# DevBoard_20240716.net
KiCad netlist of a schematic drawn in EasyEDA Pro
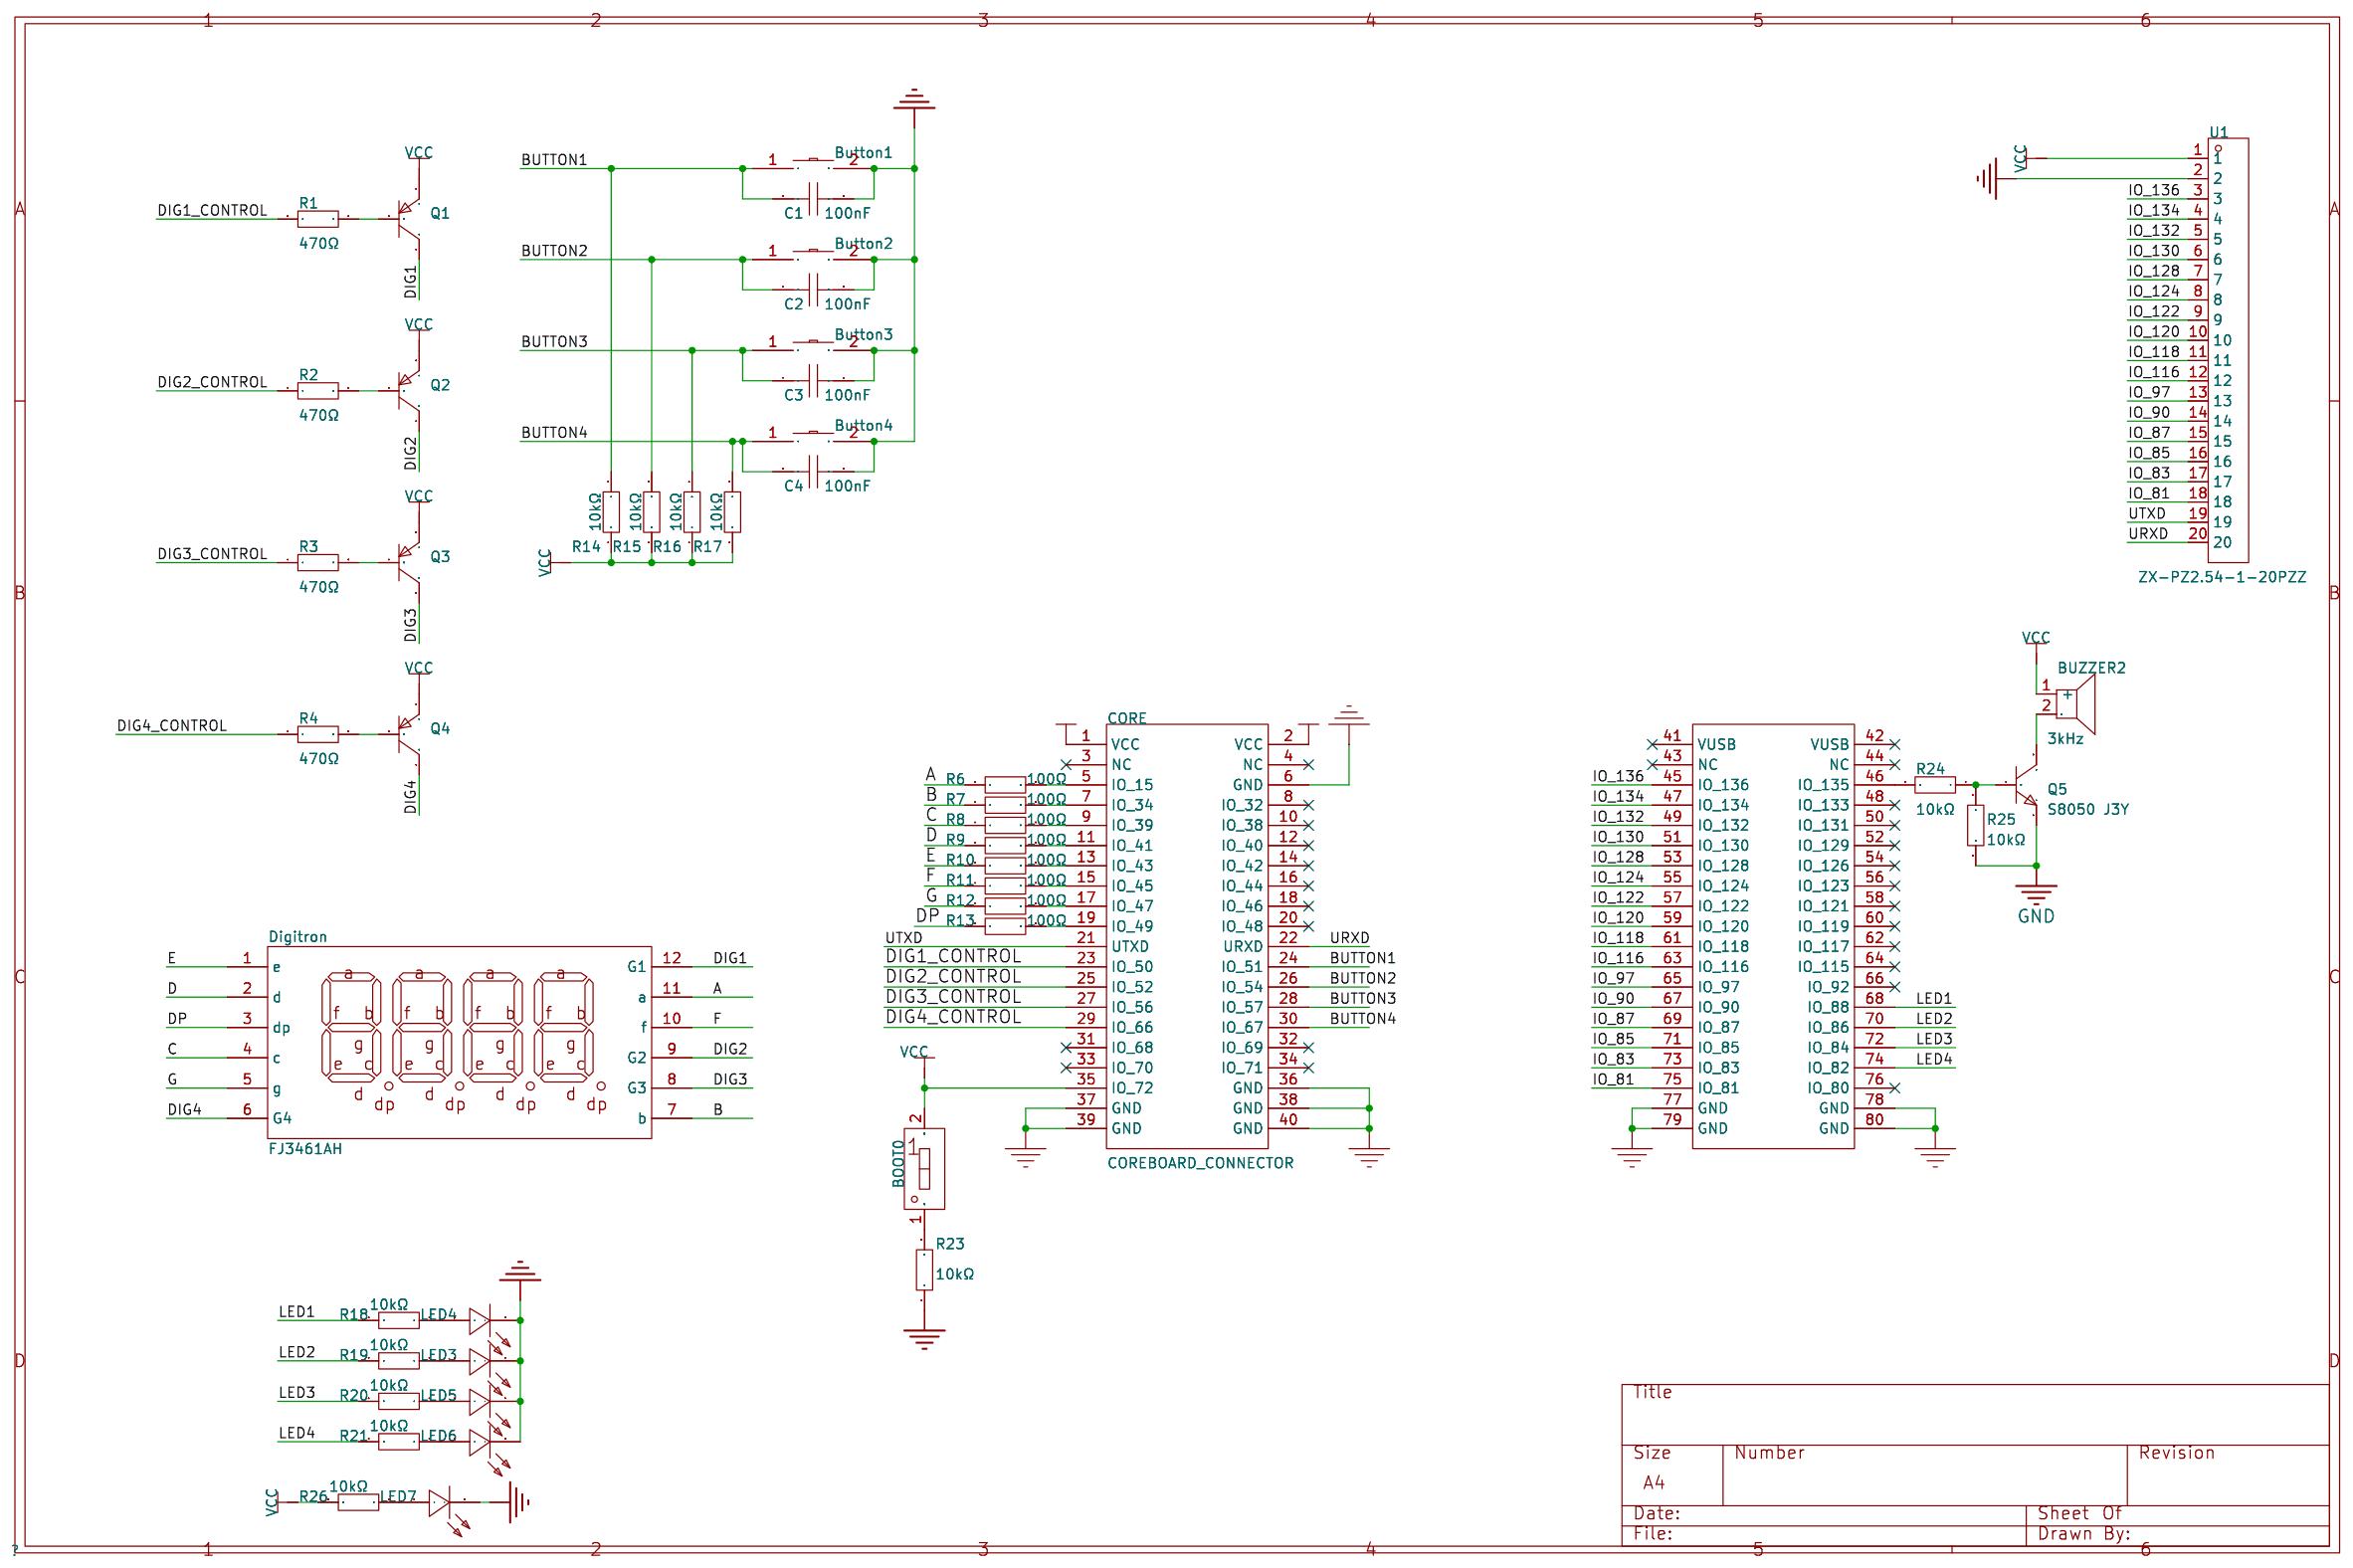
[diagram p0: schematic sheet]

(export (version "E")
  (design (tool "Eeschema 10.0.6"))
  (components
    (comp (ref "BOOT0")
      (value "DSIC01LS-P")
      (footprint "easyedapro:SW-SMD_2P-L3.5-W6.2-P2.54-LS9.8")
      (description "类型:平拨,凸起式;电路结构:单刀单掷;开关位数:1位;额定电流:25mA;额定电压:24V;使用寿命:3千次;颜色:黑色;")
      (fields (field (name "Manufacturer") "XKB Connectivity(中国星坤)"))
      (libsource (lib "easyedapro") (part "DSIC01LS-P_C600988"))
    )
    (comp (ref "Button1")
      (value "TS-1101-C-W")
      (footprint "easyedapro:SW-SMD_L6.0-W3.3-LS8.0")
      (fields (field (name "Manufacturer") "XKB Connectivity(中国星坤)"))
      (libsource (lib "easyedapro") (part "TS-1101-C-W"))
    )
    (comp (ref "Button2")
      (value "TS-1101-C-W")
      (footprint "easyedapro:SW-SMD_L6.0-W3.3-LS8.0")
      (fields (field (name "Manufacturer") "XKB Connectivity(中国星坤)"))
      (libsource (lib "easyedapro") (part "TS-1101-C-W"))
    )
    (comp (ref "Button3")
      (value "TS-1101-C-W")
      (footprint "easyedapro:SW-SMD_L6.0-W3.3-LS8.0")
      (fields (field (name "Manufacturer") "XKB Connectivity(中国星坤)"))
      (libsource (lib "easyedapro") (part "TS-1101-C-W"))
    )
    (comp (ref "Button4")
      (value "TS-1101-C-W")
      (footprint "easyedapro:SW-SMD_L6.0-W3.3-LS8.0")
      (fields (field (name "Manufacturer") "XKB Connectivity(中国星坤)"))
      (libsource (lib "easyedapro") (part "TS-1101-C-W"))
    )
    (comp (ref "BUZZER2")
      (value "3kHz")
      (footprint "easyedapro:BUZ-TH_BD9.6-P5.00-D0.7-FD")
      (description "驱动方式:有源(内含驱动线路);构造类型:电磁式;频率:3kHz;声压(SPL):85dB;")
      (fields (field (name "Manufacturer Part") "HNB09A05") (field (name "Manufacturer") "华能"))
      (libsource (lib "easyedapro") (part "HNB09A05"))
    )
    (comp (ref "C1")
      (value "100nF")
      (footprint "easyedapro:C0603")
      (description "容值:100nF;精度:±10%;额定电压:50V;材质(温度系数):X7R;")
      (fields
        (field (name "Manufacturer Part") "CC0603KRX7R9BB104")
        (field (name "Manufacturer") "YAGEO(国巨)")
      )
      (libsource (lib "easyedapro") (part "CC0603KRX7R9BB104"))
    )
    (comp (ref "C2")
      (value "100nF")
      (footprint "easyedapro:C0603")
      (description "容值:100nF;精度:±10%;额定电压:50V;材质(温度系数):X7R;")
      (fields
        (field (name "Manufacturer Part") "CC0603KRX7R9BB104")
        (field (name "Manufacturer") "YAGEO(国巨)")
      )
      (libsource (lib "easyedapro") (part "CC0603KRX7R9BB104"))
    )
    (comp (ref "C3")
      (value "100nF")
      (footprint "easyedapro:C0603")
      (description "容值:100nF;精度:±10%;额定电压:50V;材质(温度系数):X7R;")
      (fields
        (field (name "Manufacturer Part") "CC0603KRX7R9BB104")
        (field (name "Manufacturer") "YAGEO(国巨)")
      )
      (libsource (lib "easyedapro") (part "CC0603KRX7R9BB104"))
    )
    (comp (ref "C4")
      (value "100nF")
      (footprint "easyedapro:C0603")
      (description "容值:100nF;精度:±10%;额定电压:50V;材质(温度系数):X7R;")
      (fields
        (field (name "Manufacturer Part") "CC0603KRX7R9BB104")
        (field (name "Manufacturer") "YAGEO(国巨)")
      )
      (libsource (lib "easyedapro") (part "CC0603KRX7R9BB104"))
    )
    (comp (ref "CORE")
      (value "COREBOARD_CONNECTOR")
      (libsource (lib "easyedapro") (part "COREBOARD_CONNECTOR"))
    )
    (comp (ref "Digitron")
      (value "FJ3461AH")
      (footprint "easyedapro:LED-SEG-TH_12P-L30.0-W14.0-P2.54-S10.16-BL")
      (description "数码管位数:4位;功耗:-;发光颜色:红色;LED极性:共阴极;数字/字母大小(英寸):0.36;")
      (fields (field (name "Manufacturer") "志浩"))
      (libsource (lib "easyedapro") (part "FJ3461AH"))
    )
    (comp (ref "LED3")
      (value "NCD0805B2")
      (footprint "easyedapro:LED0805-R-RD")
      (fields (field (name "Manufacturer") "国星光电"))
      (libsource (lib "easyedapro") (part "FC-A2012BK-470H2"))
    )
    (comp (ref "LED4")
      (value "NCD0805B2")
      (footprint "easyedapro:LED0805-R-RD")
      (fields (field (name "Manufacturer") "国星光电"))
      (libsource (lib "easyedapro") (part "FC-A2012BK-470H2"))
    )
    (comp (ref "LED5")
      (value "NCD0805B2")
      (footprint "easyedapro:LED0805-R-RD")
      (fields (field (name "Manufacturer") "国星光电"))
      (libsource (lib "easyedapro") (part "FC-A2012BK-470H2"))
    )
    (comp (ref "LED6")
      (value "NCD0805B2")
      (footprint "easyedapro:LED0805-R-RD")
      (fields (field (name "Manufacturer") "国星光电"))
      (libsource (lib "easyedapro") (part "FC-A2012BK-470H2"))
    )
    (comp (ref "LED7")
      (value "NCD0805B2")
      (footprint "easyedapro:LED0805-R-RD")
      (fields (field (name "Manufacturer") "国星光电"))
      (libsource (lib "easyedapro") (part "FC-A2012BK-470H2"))
    )
    (comp (ref "Q1")
      (value "~")
      (footprint "easyedapro:S8550P_SOT")
      (libsource (lib "easyedapro") (part "PNP"))
    )
    (comp (ref "Q2")
      (value "~")
      (footprint "easyedapro:S8550P_SOT")
      (libsource (lib "easyedapro") (part "PNP"))
    )
    (comp (ref "Q3")
      (value "~")
      (footprint "easyedapro:S8550P_SOT")
      (libsource (lib "easyedapro") (part "PNP"))
    )
    (comp (ref "Q4")
      (value "~")
      (footprint "easyedapro:S8550P_SOT")
      (libsource (lib "easyedapro") (part "PNP"))
    )
    (comp (ref "Q5")
      (value "S8050 J3Y")
      (footprint "easyedapro:SOT-23-3_L3.0-W1.7-P0.95-LS2.9-BR")
      (description "晶体管类型:NPN;集射极击穿电压(Vceo):25V;集电极电流(Ic):500mA;功率(Pd):300mW;直流电流增益(hFE@Ic,Vce):200@50mA,1V;")
      (fields (field (name "Manufacturer") "CJ(江苏长电/长晶)"))
      (libsource (lib "easyedapro") (part "S8050_C2146"))
    )
    (comp (ref "R1")
      (value "470Ω")
      (footprint "easyedapro:R0603")
      (description "电阻类型:厚膜电阻;阻值:470Ω;精度:±1%;功率:100mW;最大工作电压:75V;温度系数:±100ppm/°C;")
      (fields
        (field (name "Manufacturer Part") "0603WAF4700T5E")
        (field (name "Manufacturer") "UNI-ROYAL(厚声)")
      )
      (libsource (lib "easyedapro") (part "0603WAF4700T5E"))
    )
    (comp (ref "R2")
      (value "470Ω")
      (footprint "easyedapro:R0603")
      (description "电阻类型:厚膜电阻;阻值:470Ω;精度:±1%;功率:100mW;最大工作电压:75V;温度系数:±100ppm/°C;")
      (fields
        (field (name "Manufacturer Part") "0603WAF4700T5E")
        (field (name "Manufacturer") "UNI-ROYAL(厚声)")
      )
      (libsource (lib "easyedapro") (part "0603WAF4700T5E"))
    )
    (comp (ref "R3")
      (value "470Ω")
      (footprint "easyedapro:R0603")
      (description "电阻类型:厚膜电阻;阻值:470Ω;精度:±1%;功率:100mW;最大工作电压:75V;温度系数:±100ppm/°C;")
      (fields
        (field (name "Manufacturer Part") "0603WAF4700T5E")
        (field (name "Manufacturer") "UNI-ROYAL(厚声)")
      )
      (libsource (lib "easyedapro") (part "0603WAF4700T5E"))
    )
    (comp (ref "R4")
      (value "470Ω")
      (footprint "easyedapro:R0603")
      (description "电阻类型:厚膜电阻;阻值:470Ω;精度:±1%;功率:100mW;最大工作电压:75V;温度系数:±100ppm/°C;")
      (fields
        (field (name "Manufacturer Part") "0603WAF4700T5E")
        (field (name "Manufacturer") "UNI-ROYAL(厚声)")
      )
      (libsource (lib "easyedapro") (part "0603WAF4700T5E"))
    )
    (comp (ref "R6")
      (value "100Ω")
      (footprint "easyedapro:R0603")
      (description "电阻类型:厚膜电阻;阻值:100Ω;精度:±1%;功率:100mW;最大工作电压:75V;温度系数:±200ppm/°C;")
      (fields
        (field (name "Manufacturer Part") "0603WAF1000T5E")
        (field (name "Manufacturer") "UNI-ROYAL(厚声)")
      )
      (libsource (lib "easyedapro") (part "0603WAF1000T5E"))
    )
    (comp (ref "R7")
      (value "100Ω")
      (footprint "easyedapro:R0603")
      (description "电阻类型:厚膜电阻;阻值:100Ω;精度:±1%;功率:100mW;最大工作电压:75V;温度系数:±200ppm/°C;")
      (fields
        (field (name "Manufacturer Part") "0603WAF1000T5E")
        (field (name "Manufacturer") "UNI-ROYAL(厚声)")
      )
      (libsource (lib "easyedapro") (part "0603WAF1000T5E"))
    )
    (comp (ref "R8")
      (value "100Ω")
      (footprint "easyedapro:R0603")
      (description "电阻类型:厚膜电阻;阻值:100Ω;精度:±1%;功率:100mW;最大工作电压:75V;温度系数:±200ppm/°C;")
      (fields
        (field (name "Manufacturer Part") "0603WAF1000T5E")
        (field (name "Manufacturer") "UNI-ROYAL(厚声)")
      )
      (libsource (lib "easyedapro") (part "0603WAF1000T5E"))
    )
    (comp (ref "R9")
      (value "100Ω")
      (footprint "easyedapro:R0603")
      (description "电阻类型:厚膜电阻;阻值:100Ω;精度:±1%;功率:100mW;最大工作电压:75V;温度系数:±200ppm/°C;")
      (fields
        (field (name "Manufacturer Part") "0603WAF1000T5E")
        (field (name "Manufacturer") "UNI-ROYAL(厚声)")
      )
      (libsource (lib "easyedapro") (part "0603WAF1000T5E"))
    )
    (comp (ref "R10")
      (value "100Ω")
      (footprint "easyedapro:R0603")
      (description "电阻类型:厚膜电阻;阻值:100Ω;精度:±1%;功率:100mW;最大工作电压:75V;温度系数:±200ppm/°C;")
      (fields
        (field (name "Manufacturer Part") "0603WAF1000T5E")
        (field (name "Manufacturer") "UNI-ROYAL(厚声)")
      )
      (libsource (lib "easyedapro") (part "0603WAF1000T5E"))
    )
    (comp (ref "R11")
      (value "100Ω")
      (footprint "easyedapro:R0603")
      (description "电阻类型:厚膜电阻;阻值:100Ω;精度:±1%;功率:100mW;最大工作电压:75V;温度系数:±200ppm/°C;")
      (fields
        (field (name "Manufacturer Part") "0603WAF1000T5E")
        (field (name "Manufacturer") "UNI-ROYAL(厚声)")
      )
      (libsource (lib "easyedapro") (part "0603WAF1000T5E"))
    )
    (comp (ref "R12")
      (value "100Ω")
      (footprint "easyedapro:R0603")
      (description "电阻类型:厚膜电阻;阻值:100Ω;精度:±1%;功率:100mW;最大工作电压:75V;温度系数:±200ppm/°C;")
      (fields
        (field (name "Manufacturer Part") "0603WAF1000T5E")
        (field (name "Manufacturer") "UNI-ROYAL(厚声)")
      )
      (libsource (lib "easyedapro") (part "0603WAF1000T5E"))
    )
    (comp (ref "R13")
      (value "100Ω")
      (footprint "easyedapro:R0603")
      (description "电阻类型:厚膜电阻;阻值:100Ω;精度:±1%;功率:100mW;最大工作电压:75V;温度系数:±200ppm/°C;")
      (fields
        (field (name "Manufacturer Part") "0603WAF1000T5E")
        (field (name "Manufacturer") "UNI-ROYAL(厚声)")
      )
      (libsource (lib "easyedapro") (part "0603WAF1000T5E"))
    )
    (comp (ref "R14")
      (value "10kΩ")
      (footprint "easyedapro:R0603")
      (description "电阻类型:厚膜电阻;阻值:10kΩ;精度:±1%;功率:100mW;最大工作电压:75V;温度系数:±100ppm/°C;")
      (fields
        (field (name "Manufacturer Part") "0603WAF1002T5E")
        (field (name "Manufacturer") "UNI-ROYAL(厚声)")
      )
      (libsource (lib "easyedapro") (part "0603WAF1002T5E"))
    )
    (comp (ref "R15")
      (value "10kΩ")
      (footprint "easyedapro:R0603")
      (description "电阻类型:厚膜电阻;阻值:10kΩ;精度:±1%;功率:100mW;最大工作电压:75V;温度系数:±100ppm/°C;")
      (fields
        (field (name "Manufacturer Part") "0603WAF1002T5E")
        (field (name "Manufacturer") "UNI-ROYAL(厚声)")
      )
      (libsource (lib "easyedapro") (part "0603WAF1002T5E"))
    )
    (comp (ref "R16")
      (value "10kΩ")
      (footprint "easyedapro:R0603")
      (description "电阻类型:厚膜电阻;阻值:10kΩ;精度:±1%;功率:100mW;最大工作电压:75V;温度系数:±100ppm/°C;")
      (fields
        (field (name "Manufacturer Part") "0603WAF1002T5E")
        (field (name "Manufacturer") "UNI-ROYAL(厚声)")
      )
      (libsource (lib "easyedapro") (part "0603WAF1002T5E"))
    )
    (comp (ref "R17")
      (value "10kΩ")
      (footprint "easyedapro:R0603")
      (description "电阻类型:厚膜电阻;阻值:10kΩ;精度:±1%;功率:100mW;最大工作电压:75V;温度系数:±100ppm/°C;")
      (fields
        (field (name "Manufacturer Part") "0603WAF1002T5E")
        (field (name "Manufacturer") "UNI-ROYAL(厚声)")
      )
      (libsource (lib "easyedapro") (part "0603WAF1002T5E"))
    )
    (comp (ref "R18")
      (value "10kΩ")
      (footprint "easyedapro:R0603")
      (description "电阻类型:厚膜电阻;阻值:10kΩ;精度:±1%;功率:100mW;最大工作电压:75V;温度系数:±100ppm/°C;")
      (fields
        (field (name "Manufacturer Part") "0603WAF1002T5E")
        (field (name "Manufacturer") "UNI-ROYAL(厚声)")
      )
      (libsource (lib "easyedapro") (part "0603WAF1002T5E"))
    )
    (comp (ref "R19")
      (value "10kΩ")
      (footprint "easyedapro:R0603")
      (description "电阻类型:厚膜电阻;阻值:10kΩ;精度:±1%;功率:100mW;最大工作电压:75V;温度系数:±100ppm/°C;")
      (fields
        (field (name "Manufacturer Part") "0603WAF1002T5E")
        (field (name "Manufacturer") "UNI-ROYAL(厚声)")
      )
      (libsource (lib "easyedapro") (part "0603WAF1002T5E"))
    )
    (comp (ref "R20")
      (value "10kΩ")
      (footprint "easyedapro:R0603")
      (description "电阻类型:厚膜电阻;阻值:10kΩ;精度:±1%;功率:100mW;最大工作电压:75V;温度系数:±100ppm/°C;")
      (fields
        (field (name "Manufacturer Part") "0603WAF1002T5E")
        (field (name "Manufacturer") "UNI-ROYAL(厚声)")
      )
      (libsource (lib "easyedapro") (part "0603WAF1002T5E"))
    )
    (comp (ref "R21")
      (value "10kΩ")
      (footprint "easyedapro:R0603")
      (description "电阻类型:厚膜电阻;阻值:10kΩ;精度:±1%;功率:100mW;最大工作电压:75V;温度系数:±100ppm/°C;")
      (fields
        (field (name "Manufacturer Part") "0603WAF1002T5E")
        (field (name "Manufacturer") "UNI-ROYAL(厚声)")
      )
      (libsource (lib "easyedapro") (part "0603WAF1002T5E"))
    )
    (comp (ref "R23")
      (value "10kΩ")
      (footprint "easyedapro:R0603")
      (description "电阻类型:厚膜电阻;阻值:10kΩ;精度:±1%;功率:100mW;最大工作电压:75V;温度系数:±100ppm/°C;")
      (fields
        (field (name "Manufacturer Part") "0603WAF1002T5E")
        (field (name "Manufacturer") "UNI-ROYAL(厚声)")
      )
      (libsource (lib "easyedapro") (part "0603WAF1002T5E"))
    )
    (comp (ref "R24")
      (value "10kΩ")
      (footprint "easyedapro:R0805")
      (description "阻值:10kΩ;精度:±1%;功率:125mW;温度系数:±100ppm/°C;电阻类型:厚膜电阻;")
      (fields
        (field (name "Manufacturer Part") "0805W8F1002T5E")
        (field (name "Manufacturer") "UNI-ROYAL(厚声)")
      )
      (libsource (lib "easyedapro") (part "0805W8F1002T5E"))
    )
    (comp (ref "R25")
      (value "10kΩ")
      (footprint "easyedapro:R0805")
      (description "阻值:10kΩ;精度:±1%;功率:125mW;温度系数:±100ppm/°C;电阻类型:厚膜电阻;")
      (fields
        (field (name "Manufacturer Part") "0805W8F1002T5E")
        (field (name "Manufacturer") "UNI-ROYAL(厚声)")
      )
      (libsource (lib "easyedapro") (part "0805W8F1002T5E"))
    )
    (comp (ref "R26")
      (value "10kΩ")
      (footprint "easyedapro:R0603")
      (description "电阻类型:厚膜电阻;阻值:10kΩ;精度:±1%;功率:100mW;最大工作电压:75V;温度系数:±100ppm/°C;")
      (fields
        (field (name "Manufacturer Part") "0603WAF1002T5E")
        (field (name "Manufacturer") "UNI-ROYAL(厚声)")
      )
      (libsource (lib "easyedapro") (part "0603WAF1002T5E"))
    )
    (comp (ref "U1")
      (value "ZX-PZ2.54-1-20PZZ")
      (footprint "easyedapro:HDR-TH_20P-P2.54-V-M")
      (fields (field (name "Manufacturer") "Megastar(兆星)"))
      (libsource (lib "easyedapro") (part "ZX-PZ2.54-1-20PZZ"))
    )
  )
  (nets
    (net (code "1") (name "/A") (class "Default")
      (node (ref "Digitron") (pin "11") (pinfunction "a_11") (pintype "input"))
      (node (ref "R6") (pin "1") (pinfunction "1_1") (pintype "input"))
    )
    (net (code "2") (name "/B") (class "Default")
      (node (ref "Digitron") (pin "7") (pinfunction "b_7") (pintype "input"))
      (node (ref "R7") (pin "1") (pinfunction "1_1") (pintype "input"))
    )
    (net (code "3") (name "/BUTTON1") (class "Default")
      (node (ref "Button1") (pin "1") (pinfunction "1_1") (pintype "unspecified"))
      (node (ref "C1") (pin "1") (pinfunction "1_1") (pintype "unspecified"))
      (node (ref "CORE") (pin "24") (pinfunction "IO_51_24") (pintype "unspecified"))
      (node (ref "R14") (pin "2") (pinfunction "2_2") (pintype "input"))
    )
    (net (code "4") (name "/BUTTON2") (class "Default")
      (node (ref "Button2") (pin "1") (pinfunction "1_1") (pintype "unspecified"))
      (node (ref "C2") (pin "1") (pinfunction "1_1") (pintype "unspecified"))
      (node (ref "CORE") (pin "26") (pinfunction "IO_54_26") (pintype "unspecified"))
      (node (ref "R15") (pin "2") (pinfunction "2_2") (pintype "input"))
    )
    (net (code "5") (name "/BUTTON3") (class "Default")
      (node (ref "Button3") (pin "1") (pinfunction "1_1") (pintype "unspecified"))
      (node (ref "C3") (pin "1") (pinfunction "1_1") (pintype "unspecified"))
      (node (ref "CORE") (pin "28") (pinfunction "IO_57_28") (pintype "unspecified"))
      (node (ref "R16") (pin "2") (pinfunction "2_2") (pintype "input"))
    )
    (net (code "6") (name "/BUTTON4") (class "Default")
      (node (ref "Button4") (pin "1") (pinfunction "1_1") (pintype "unspecified"))
      (node (ref "C4") (pin "1") (pinfunction "1_1") (pintype "unspecified"))
      (node (ref "CORE") (pin "30") (pinfunction "IO_67_30") (pintype "unspecified"))
      (node (ref "R17") (pin "2") (pinfunction "2_2") (pintype "input"))
    )
    (net (code "7") (name "/C") (class "Default")
      (node (ref "Digitron") (pin "4") (pinfunction "c_4") (pintype "input"))
      (node (ref "R8") (pin "1") (pinfunction "1_1") (pintype "input"))
    )
    (net (code "8") (name "/D") (class "Default")
      (node (ref "Digitron") (pin "2") (pinfunction "d_2") (pintype "input"))
      (node (ref "R9") (pin "1") (pinfunction "1_1") (pintype "input"))
    )
    (net (code "9") (name "/DIG1") (class "Default")
      (node (ref "Digitron") (pin "12") (pinfunction "G1_12") (pintype "input"))
      (node (ref "Q1") (pin "3") (pinfunction "C_3") (pintype "input"))
    )
    (net (code "10") (name "/DIG1_CONTROL") (class "Default")
      (node (ref "CORE") (pin "23") (pinfunction "IO_50_23") (pintype "unspecified"))
      (node (ref "R1") (pin "2") (pinfunction "2_2") (pintype "input"))
    )
    (net (code "11") (name "/DIG2") (class "Default")
      (node (ref "Digitron") (pin "9") (pinfunction "G2_9") (pintype "input"))
      (node (ref "Q2") (pin "3") (pinfunction "C_3") (pintype "input"))
    )
    (net (code "12") (name "/DIG2_CONTROL") (class "Default")
      (node (ref "CORE") (pin "25") (pinfunction "IO_52_25") (pintype "unspecified"))
      (node (ref "R2") (pin "1") (pinfunction "1_1") (pintype "input"))
    )
    (net (code "13") (name "/DIG3") (class "Default")
      (node (ref "Digitron") (pin "8") (pinfunction "G3_8") (pintype "input"))
      (node (ref "Q3") (pin "3") (pinfunction "C_3") (pintype "input"))
    )
    (net (code "14") (name "/DIG3_CONTROL") (class "Default")
      (node (ref "CORE") (pin "27") (pinfunction "IO_56_27") (pintype "unspecified"))
      (node (ref "R3") (pin "1") (pinfunction "1_1") (pintype "input"))
    )
    (net (code "15") (name "/DIG4") (class "Default")
      (node (ref "Digitron") (pin "6") (pinfunction "G4_6") (pintype "input"))
      (node (ref "Q4") (pin "3") (pinfunction "C_3") (pintype "input"))
    )
    (net (code "16") (name "/DIG4_CONTROL") (class "Default")
      (node (ref "CORE") (pin "29") (pinfunction "IO_66_29") (pintype "unspecified"))
      (node (ref "R4") (pin "1") (pinfunction "1_1") (pintype "input"))
    )
    (net (code "17") (name "/DP") (class "Default")
      (node (ref "Digitron") (pin "3") (pinfunction "dp_3") (pintype "input"))
      (node (ref "R13") (pin "1") (pinfunction "1_1") (pintype "input"))
    )
    (net (code "18") (name "/E") (class "Default")
      (node (ref "Digitron") (pin "1") (pinfunction "e_1") (pintype "input"))
      (node (ref "R10") (pin "1") (pinfunction "1_1") (pintype "input"))
    )
    (net (code "19") (name "/F") (class "Default")
      (node (ref "Digitron") (pin "10") (pinfunction "f_10") (pintype "input"))
      (node (ref "R11") (pin "1") (pinfunction "1_1") (pintype "input"))
    )
    (net (code "20") (name "/G") (class "Default")
      (node (ref "Digitron") (pin "5") (pinfunction "g_5") (pintype "input"))
      (node (ref "R12") (pin "1") (pinfunction "1_1") (pintype "input"))
    )
    (net (code "21") (name "/IO_81") (class "Default")
      (node (ref "CORE") (pin "75") (pinfunction "IO_81_75") (pintype "unspecified"))
      (node (ref "U1") (pin "18") (pinfunction "18_18") (pintype "unspecified"))
    )
    (net (code "22") (name "/IO_83") (class "Default")
      (node (ref "CORE") (pin "73") (pinfunction "IO_83_73") (pintype "unspecified"))
      (node (ref "U1") (pin "17") (pinfunction "17_17") (pintype "unspecified"))
    )
    (net (code "23") (name "/IO_85") (class "Default")
      (node (ref "CORE") (pin "71") (pinfunction "IO_85_71") (pintype "unspecified"))
      (node (ref "U1") (pin "16") (pinfunction "16_16") (pintype "unspecified"))
    )
    (net (code "24") (name "/IO_87") (class "Default")
      (node (ref "CORE") (pin "69") (pinfunction "IO_87_69") (pintype "unspecified"))
      (node (ref "U1") (pin "15") (pinfunction "15_15") (pintype "unspecified"))
    )
    (net (code "25") (name "/IO_90") (class "Default")
      (node (ref "CORE") (pin "67") (pinfunction "IO_90_67") (pintype "unspecified"))
      (node (ref "U1") (pin "14") (pinfunction "14_14") (pintype "unspecified"))
    )
    (net (code "26") (name "/IO_97") (class "Default")
      (node (ref "CORE") (pin "65") (pinfunction "IO_97_65") (pintype "unspecified"))
      (node (ref "U1") (pin "13") (pinfunction "13_13") (pintype "unspecified"))
    )
    (net (code "27") (name "/IO_116") (class "Default")
      (node (ref "CORE") (pin "63") (pinfunction "IO_116_63") (pintype "unspecified"))
      (node (ref "U1") (pin "12") (pinfunction "12_12") (pintype "unspecified"))
    )
    (net (code "28") (name "/IO_118") (class "Default")
      (node (ref "CORE") (pin "61") (pinfunction "IO_118_61") (pintype "unspecified"))
      (node (ref "U1") (pin "11") (pinfunction "11_11") (pintype "unspecified"))
    )
    (net (code "29") (name "/IO_120") (class "Default")
      (node (ref "CORE") (pin "59") (pinfunction "IO_120_59") (pintype "unspecified"))
      (node (ref "U1") (pin "10") (pinfunction "10_10") (pintype "unspecified"))
    )
    (net (code "30") (name "/IO_122") (class "Default")
      (node (ref "CORE") (pin "57") (pinfunction "IO_122_57") (pintype "unspecified"))
      (node (ref "U1") (pin "9") (pinfunction "9_9") (pintype "unspecified"))
    )
    (net (code "31") (name "/IO_124") (class "Default")
      (node (ref "CORE") (pin "55") (pinfunction "IO_124_55") (pintype "unspecified"))
      (node (ref "U1") (pin "8") (pinfunction "8_8") (pintype "unspecified"))
    )
    (net (code "32") (name "/IO_128") (class "Default")
      (node (ref "CORE") (pin "53") (pinfunction "IO_128_53") (pintype "unspecified"))
      (node (ref "U1") (pin "7") (pinfunction "7_7") (pintype "unspecified"))
    )
    (net (code "33") (name "/IO_130") (class "Default")
      (node (ref "CORE") (pin "51") (pinfunction "IO_130_51") (pintype "unspecified"))
      (node (ref "U1") (pin "6") (pinfunction "6_6") (pintype "unspecified"))
    )
    (net (code "34") (name "/IO_132") (class "Default")
      (node (ref "CORE") (pin "49") (pinfunction "IO_132_49") (pintype "unspecified"))
      (node (ref "U1") (pin "5") (pinfunction "5_5") (pintype "unspecified"))
    )
    (net (code "35") (name "/IO_134") (class "Default")
      (node (ref "CORE") (pin "47") (pinfunction "IO_134_47") (pintype "unspecified"))
      (node (ref "U1") (pin "4") (pinfunction "4_4") (pintype "unspecified"))
    )
    (net (code "36") (name "/IO_136") (class "Default")
      (node (ref "CORE") (pin "45") (pinfunction "IO_136_45") (pintype "unspecified"))
      (node (ref "U1") (pin "3") (pinfunction "3_3") (pintype "unspecified"))
    )
    (net (code "37") (name "/LED1") (class "Default")
      (node (ref "CORE") (pin "68") (pinfunction "IO_88_68") (pintype "unspecified"))
      (node (ref "R18") (pin "2") (pinfunction "2_2") (pintype "input"))
    )
    (net (code "38") (name "/LED2") (class "Default")
      (node (ref "CORE") (pin "70") (pinfunction "IO_86_70") (pintype "unspecified"))
      (node (ref "R19") (pin "2") (pinfunction "2_2") (pintype "input"))
    )
    (net (code "39") (name "/LED3") (class "Default")
      (node (ref "CORE") (pin "72") (pinfunction "IO_84_72") (pintype "unspecified"))
      (node (ref "R20") (pin "2") (pinfunction "2_2") (pintype "input"))
    )
    (net (code "40") (name "/LED4") (class "Default")
      (node (ref "CORE") (pin "74") (pinfunction "IO_82_74") (pintype "unspecified"))
      (node (ref "R21") (pin "2") (pinfunction "2_2") (pintype "input"))
    )
    (net (code "41") (name "/URXD") (class "Default")
      (node (ref "CORE") (pin "22") (pinfunction "URXD_22") (pintype "unspecified"))
      (node (ref "U1") (pin "20") (pinfunction "20_20") (pintype "unspecified"))
    )
    (net (code "42") (name "/UTXD") (class "Default")
      (node (ref "CORE") (pin "21") (pinfunction "UTXD_21") (pintype "unspecified"))
      (node (ref "U1") (pin "19") (pinfunction "19_19") (pintype "unspecified"))
    )
    (net (code "43") (name "GND") (class "Default")
      (node (ref "Button1") (pin "2") (pinfunction "2_2") (pintype "unspecified"))
      (node (ref "Button2") (pin "2") (pinfunction "2_2") (pintype "unspecified"))
      (node (ref "Button3") (pin "2") (pinfunction "2_2") (pintype "unspecified"))
      (node (ref "Button4") (pin "2") (pinfunction "2_2") (pintype "unspecified"))
      (node (ref "C1") (pin "2") (pinfunction "2_2") (pintype "unspecified"))
      (node (ref "C2") (pin "2") (pinfunction "2_2") (pintype "unspecified"))
      (node (ref "C3") (pin "2") (pinfunction "2_2") (pintype "unspecified"))
      (node (ref "C4") (pin "2") (pinfunction "2_2") (pintype "unspecified"))
      (node (ref "CORE") (pin "36") (pinfunction "GND_36") (pintype "unspecified"))
      (node (ref "CORE") (pin "37") (pinfunction "GND_37") (pintype "unspecified"))
      (node (ref "CORE") (pin "38") (pinfunction "GND_38") (pintype "unspecified"))
      (node (ref "CORE") (pin "39") (pinfunction "GND_39") (pintype "unspecified"))
      (node (ref "CORE") (pin "40") (pinfunction "GND_40") (pintype "unspecified"))
      (node (ref "CORE") (pin "6") (pinfunction "GND_6") (pintype "unspecified"))
      (node (ref "CORE") (pin "77") (pinfunction "GND_77") (pintype "unspecified"))
      (node (ref "CORE") (pin "78") (pinfunction "GND_78") (pintype "unspecified"))
      (node (ref "CORE") (pin "79") (pinfunction "GND_79") (pintype "unspecified"))
      (node (ref "CORE") (pin "80") (pinfunction "GND_80") (pintype "unspecified"))
      (node (ref "LED3") (pin "2") (pinfunction "-_2") (pintype "unspecified"))
      (node (ref "LED4") (pin "2") (pinfunction "-_2") (pintype "unspecified"))
      (node (ref "LED5") (pin "2") (pinfunction "-_2") (pintype "unspecified"))
      (node (ref "LED6") (pin "2") (pinfunction "-_2") (pintype "unspecified"))
      (node (ref "LED7") (pin "2") (pinfunction "-_2") (pintype "unspecified"))
      (node (ref "Q5") (pin "2") (pinfunction "E_2") (pintype "unspecified"))
      (node (ref "R23") (pin "1") (pinfunction "1_1") (pintype "input"))
      (node (ref "R25") (pin "2") (pinfunction "2_2") (pintype "input"))
      (node (ref "U1") (pin "2") (pinfunction "2_2") (pintype "unspecified"))
    )
    (net (code "44") (name "Net-(BOOT0-PIN1)") (class "Default")
      (node (ref "BOOT0") (pin "1") (pinfunction "PIN1_1") (pintype "unspecified"))
      (node (ref "R23") (pin "2") (pinfunction "2_2") (pintype "input"))
    )
    (net (code "45") (name "Net-(CORE-IO_15)") (class "Default")
      (node (ref "CORE") (pin "5") (pinfunction "IO_15_5") (pintype "unspecified"))
      (node (ref "R6") (pin "2") (pinfunction "2_2") (pintype "input"))
    )
    (net (code "46") (name "Net-(CORE-IO_34)") (class "Default")
      (node (ref "CORE") (pin "7") (pinfunction "IO_34_7") (pintype "unspecified"))
      (node (ref "R7") (pin "2") (pinfunction "2_2") (pintype "input"))
    )
    (net (code "47") (name "Net-(CORE-IO_39)") (class "Default")
      (node (ref "CORE") (pin "9") (pinfunction "IO_39_9") (pintype "unspecified"))
      (node (ref "R8") (pin "2") (pinfunction "2_2") (pintype "input"))
    )
    (net (code "48") (name "Net-(CORE-IO_41)") (class "Default")
      (node (ref "CORE") (pin "11") (pinfunction "IO_41_11") (pintype "unspecified"))
      (node (ref "R9") (pin "2") (pinfunction "2_2") (pintype "input"))
    )
    (net (code "49") (name "Net-(CORE-IO_43)") (class "Default")
      (node (ref "CORE") (pin "13") (pinfunction "IO_43_13") (pintype "unspecified"))
      (node (ref "R10") (pin "2") (pinfunction "2_2") (pintype "input"))
    )
    (net (code "50") (name "Net-(CORE-IO_45)") (class "Default")
      (node (ref "CORE") (pin "15") (pinfunction "IO_45_15") (pintype "unspecified"))
      (node (ref "R11") (pin "2") (pinfunction "2_2") (pintype "input"))
    )
    (net (code "51") (name "Net-(CORE-IO_47)") (class "Default")
      (node (ref "CORE") (pin "17") (pinfunction "IO_47_17") (pintype "unspecified"))
      (node (ref "R12") (pin "2") (pinfunction "2_2") (pintype "input"))
    )
    (net (code "52") (name "Net-(CORE-IO_49)") (class "Default")
      (node (ref "CORE") (pin "19") (pinfunction "IO_49_19") (pintype "unspecified"))
      (node (ref "R13") (pin "2") (pinfunction "2_2") (pintype "input"))
    )
    (net (code "53") (name "Net-(CORE-IO_135)") (class "Default")
      (node (ref "CORE") (pin "46") (pinfunction "IO_135_46") (pintype "unspecified"))
      (node (ref "R24") (pin "2") (pinfunction "2_2") (pintype "input"))
    )
    (net (code "54") (name "Net-(LED3-+)") (class "Default")
      (node (ref "LED3") (pin "1") (pinfunction "+_1") (pintype "unspecified"))
      (node (ref "R19") (pin "1") (pinfunction "1_1") (pintype "input"))
    )
    (net (code "55") (name "Net-(LED4-+)") (class "Default")
      (node (ref "LED4") (pin "1") (pinfunction "+_1") (pintype "unspecified"))
      (node (ref "R18") (pin "1") (pinfunction "1_1") (pintype "input"))
    )
    (net (code "56") (name "Net-(LED5-+)") (class "Default")
      (node (ref "LED5") (pin "1") (pinfunction "+_1") (pintype "unspecified"))
      (node (ref "R20") (pin "1") (pinfunction "1_1") (pintype "input"))
    )
    (net (code "57") (name "Net-(LED6-+)") (class "Default")
      (node (ref "LED6") (pin "1") (pinfunction "+_1") (pintype "unspecified"))
      (node (ref "R21") (pin "1") (pinfunction "1_1") (pintype "input"))
    )
    (net (code "58") (name "Net-(LED7-+)") (class "Default")
      (node (ref "LED7") (pin "1") (pinfunction "+_1") (pintype "unspecified"))
      (node (ref "R26") (pin "1") (pinfunction "1_1") (pintype "input"))
    )
    (net (code "59") (name "Net-(Q1-B)") (class "Default")
      (node (ref "Q1") (pin "1") (pinfunction "B_1") (pintype "input"))
      (node (ref "R1") (pin "1") (pinfunction "1_1") (pintype "input"))
    )
    (net (code "60") (name "Net-(Q2-B)") (class "Default")
      (node (ref "Q2") (pin "1") (pinfunction "B_1") (pintype "input"))
      (node (ref "R2") (pin "2") (pinfunction "2_2") (pintype "input"))
    )
    (net (code "61") (name "Net-(Q3-B)") (class "Default")
      (node (ref "Q3") (pin "1") (pinfunction "B_1") (pintype "input"))
      (node (ref "R3") (pin "2") (pinfunction "2_2") (pintype "input"))
    )
    (net (code "62") (name "Net-(Q4-B)") (class "Default")
      (node (ref "Q4") (pin "1") (pinfunction "B_1") (pintype "input"))
      (node (ref "R4") (pin "2") (pinfunction "2_2") (pintype "input"))
    )
    (net (code "63") (name "Net-(Q5-B)") (class "Default")
      (node (ref "Q5") (pin "1") (pinfunction "B_1") (pintype "unspecified"))
      (node (ref "R24") (pin "1") (pinfunction "1_1") (pintype "input"))
      (node (ref "R25") (pin "1") (pinfunction "1_1") (pintype "input"))
    )
    (net (code "64") (name "Net-(Q5-C)") (class "Default")
      (node (ref "BUZZER2") (pin "2") (pinfunction "2_2") (pintype "unspecified"))
      (node (ref "Q5") (pin "3") (pinfunction "C_3") (pintype "unspecified"))
    )
    (net (code "65") (name "VCC") (class "Default")
      (node (ref "BOOT0") (pin "2") (pinfunction "PIN2_2") (pintype "unspecified"))
      (node (ref "BUZZER2") (pin "1") (pinfunction "+_1") (pintype "unspecified"))
      (node (ref "CORE") (pin "1") (pinfunction "VCC_1") (pintype "unspecified"))
      (node (ref "CORE") (pin "2") (pinfunction "VCC_2") (pintype "unspecified"))
      (node (ref "CORE") (pin "35") (pinfunction "IO_72_35") (pintype "unspecified"))
      (node (ref "Q1") (pin "2") (pinfunction "E_2") (pintype "input"))
      (node (ref "Q2") (pin "2") (pinfunction "E_2") (pintype "input"))
      (node (ref "Q3") (pin "2") (pinfunction "E_2") (pintype "input"))
      (node (ref "Q4") (pin "2") (pinfunction "E_2") (pintype "input"))
      (node (ref "R14") (pin "1") (pinfunction "1_1") (pintype "input"))
      (node (ref "R15") (pin "1") (pinfunction "1_1") (pintype "input"))
      (node (ref "R16") (pin "1") (pinfunction "1_1") (pintype "input"))
      (node (ref "R17") (pin "1") (pinfunction "1_1") (pintype "input"))
      (node (ref "R26") (pin "2") (pinfunction "2_2") (pintype "input"))
      (node (ref "U1") (pin "1") (pinfunction "1_1") (pintype "unspecified"))
    )
    (net (code "66") (name "unconnected-(CORE-IO_32-Pad8)") (class "Default")
      (node (ref "CORE") (pin "8") (pinfunction "IO_32_8") (pintype "unspecified+no_connect"))
    )
    (net (code "67") (name "unconnected-(CORE-IO_38-Pad10)") (class "Default")
      (node (ref "CORE") (pin "10") (pinfunction "IO_38_10") (pintype "unspecified+no_connect"))
    )
    (net (code "68") (name "unconnected-(CORE-IO_40-Pad12)") (class "Default")
      (node (ref "CORE") (pin "12") (pinfunction "IO_40_12") (pintype "unspecified+no_connect"))
    )
    (net (code "69") (name "unconnected-(CORE-IO_42-Pad14)") (class "Default")
      (node (ref "CORE") (pin "14") (pinfunction "IO_42_14") (pintype "unspecified+no_connect"))
    )
    (net (code "70") (name "unconnected-(CORE-IO_44-Pad16)") (class "Default")
      (node (ref "CORE") (pin "16") (pinfunction "IO_44_16") (pintype "unspecified+no_connect"))
    )
    (net (code "71") (name "unconnected-(CORE-IO_46-Pad18)") (class "Default")
      (node (ref "CORE") (pin "18") (pinfunction "IO_46_18") (pintype "unspecified+no_connect"))
    )
    (net (code "72") (name "unconnected-(CORE-IO_48-Pad20)") (class "Default")
      (node (ref "CORE") (pin "20") (pinfunction "IO_48_20") (pintype "unspecified+no_connect"))
    )
    (net (code "73") (name "unconnected-(CORE-IO_68-Pad31)") (class "Default")
      (node (ref "CORE") (pin "31") (pinfunction "IO_68_31") (pintype "unspecified+no_connect"))
    )
    (net (code "74") (name "unconnected-(CORE-IO_69-Pad32)") (class "Default")
      (node (ref "CORE") (pin "32") (pinfunction "IO_69_32") (pintype "unspecified+no_connect"))
    )
    (net (code "75") (name "unconnected-(CORE-IO_70-Pad33)") (class "Default")
      (node (ref "CORE") (pin "33") (pinfunction "IO_70_33") (pintype "unspecified+no_connect"))
    )
    (net (code "76") (name "unconnected-(CORE-IO_71-Pad34)") (class "Default")
      (node (ref "CORE") (pin "34") (pinfunction "IO_71_34") (pintype "unspecified+no_connect"))
    )
    (net (code "77") (name "unconnected-(CORE-IO_80-Pad76)") (class "Default")
      (node (ref "CORE") (pin "76") (pinfunction "IO_80_76") (pintype "unspecified+no_connect"))
    )
    (net (code "78") (name "unconnected-(CORE-IO_92-Pad66)") (class "Default")
      (node (ref "CORE") (pin "66") (pinfunction "IO_92_66") (pintype "unspecified+no_connect"))
    )
    (net (code "79") (name "unconnected-(CORE-IO_115-Pad64)") (class "Default")
      (node (ref "CORE") (pin "64") (pinfunction "IO_115_64") (pintype "unspecified+no_connect"))
    )
    (net (code "80") (name "unconnected-(CORE-IO_117-Pad62)") (class "Default")
      (node (ref "CORE") (pin "62") (pinfunction "IO_117_62") (pintype "unspecified+no_connect"))
    )
    (net (code "81") (name "unconnected-(CORE-IO_119-Pad60)") (class "Default")
      (node (ref "CORE") (pin "60") (pinfunction "IO_119_60") (pintype "unspecified+no_connect"))
    )
    (net (code "82") (name "unconnected-(CORE-IO_121-Pad58)") (class "Default")
      (node (ref "CORE") (pin "58") (pinfunction "IO_121_58") (pintype "unspecified+no_connect"))
    )
    (net (code "83") (name "unconnected-(CORE-IO_123-Pad56)") (class "Default")
      (node (ref "CORE") (pin "56") (pinfunction "IO_123_56") (pintype "unspecified+no_connect"))
    )
    (net (code "84") (name "unconnected-(CORE-IO_126-Pad54)") (class "Default")
      (node (ref "CORE") (pin "54") (pinfunction "IO_126_54") (pintype "unspecified+no_connect"))
    )
    (net (code "85") (name "unconnected-(CORE-IO_129-Pad52)") (class "Default")
      (node (ref "CORE") (pin "52") (pinfunction "IO_129_52") (pintype "unspecified+no_connect"))
    )
    (net (code "86") (name "unconnected-(CORE-IO_131-Pad50)") (class "Default")
      (node (ref "CORE") (pin "50") (pinfunction "IO_131_50") (pintype "unspecified+no_connect"))
    )
    (net (code "87") (name "unconnected-(CORE-IO_133-Pad48)") (class "Default")
      (node (ref "CORE") (pin "48") (pinfunction "IO_133_48") (pintype "unspecified+no_connect"))
    )
    (net (code "88") (name "unconnected-(CORE-NC-Pad3)") (class "Default")
      (node (ref "CORE") (pin "3") (pinfunction "NC_3") (pintype "unspecified+no_connect"))
    )
    (net (code "89") (name "unconnected-(CORE-NC-Pad4)") (class "Default")
      (node (ref "CORE") (pin "4") (pinfunction "NC_4") (pintype "unspecified+no_connect"))
    )
    (net (code "90") (name "unconnected-(CORE-NC-Pad43)") (class "Default")
      (node (ref "CORE") (pin "43") (pinfunction "NC_43") (pintype "unspecified+no_connect"))
    )
    (net (code "91") (name "unconnected-(CORE-NC-Pad44)") (class "Default")
      (node (ref "CORE") (pin "44") (pinfunction "NC_44") (pintype "unspecified+no_connect"))
    )
    (net (code "92") (name "unconnected-(CORE-VUSB-Pad41)") (class "Default")
      (node (ref "CORE") (pin "41") (pinfunction "VUSB_41") (pintype "unspecified+no_connect"))
    )
    (net (code "93") (name "unconnected-(CORE-VUSB-Pad42)") (class "Default")
      (node (ref "CORE") (pin "42") (pinfunction "VUSB_42") (pintype "unspecified+no_connect"))
    )
  )
)
